# MBedRoom_BaseBoard.net
KiCad netlist of a schematic drawn in EasyEDA
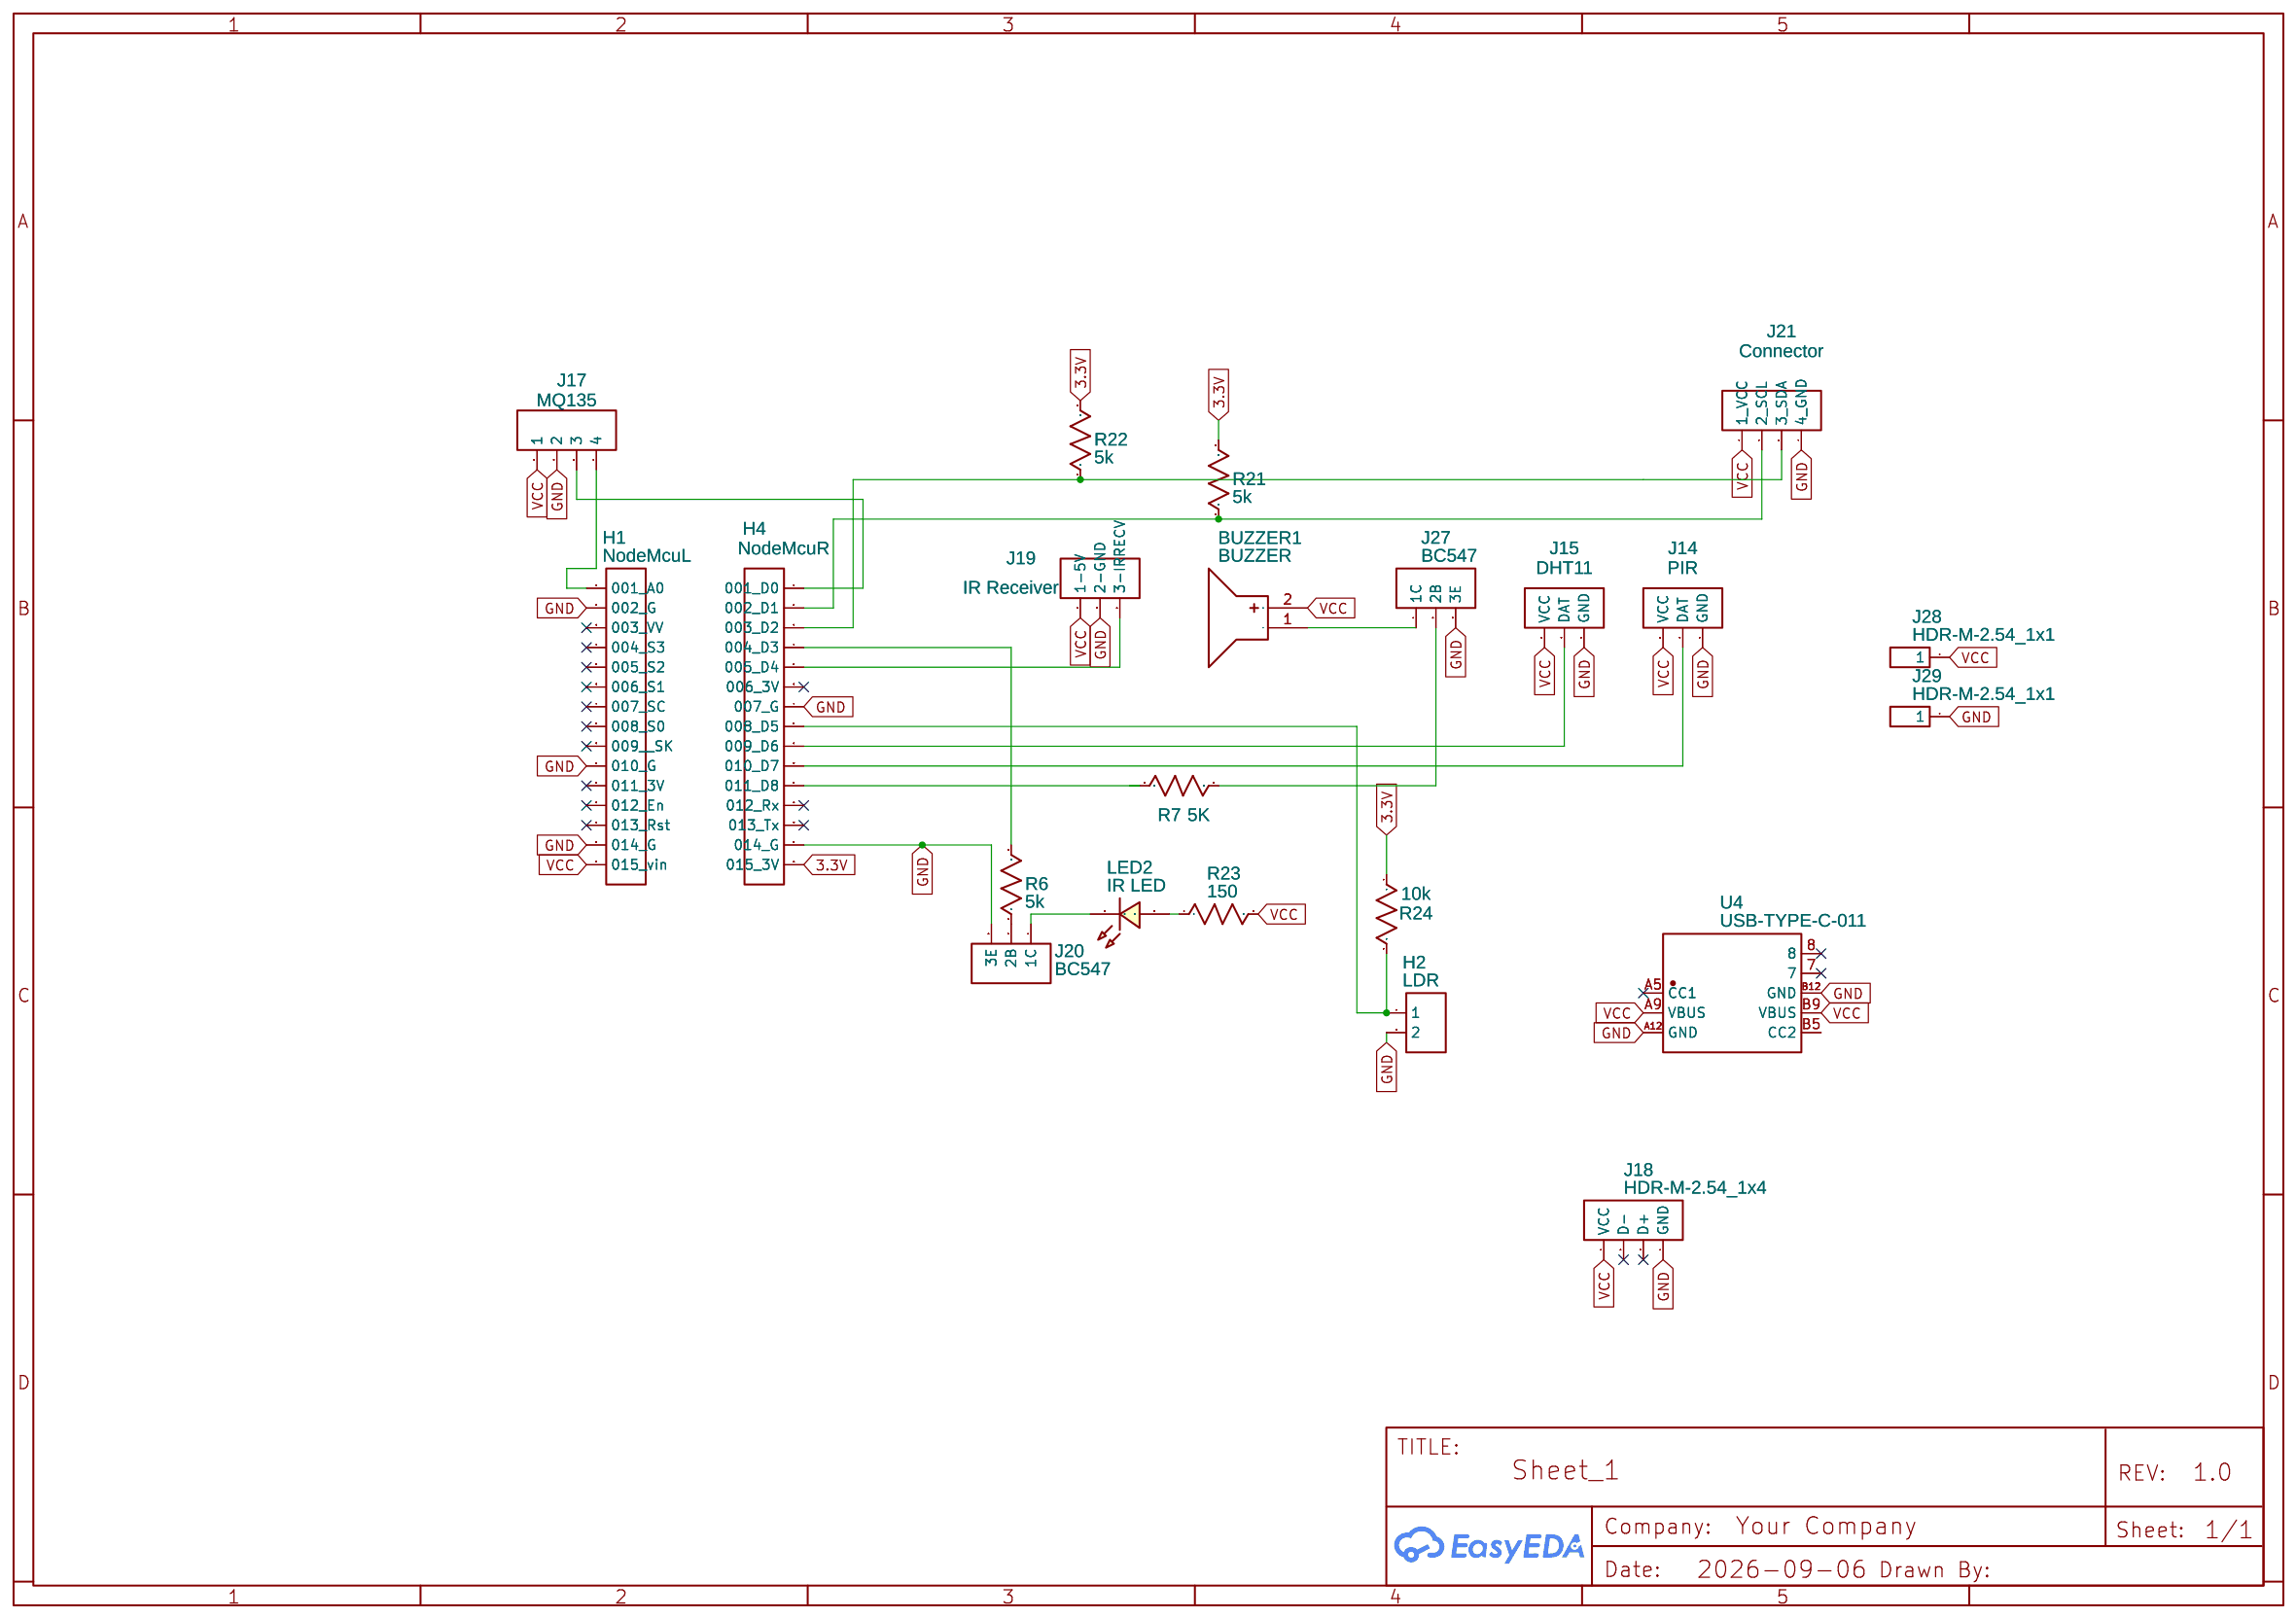
[diagram p0: schematic sheet]

(export (version "E")
  (design (tool "Eeschema 10.0.6"))
  (components
    (comp (ref "BUZZER1")
      (value "BUZZER")
      (fields (field (name "Manufacturer Part") "buzzer"))
      (libsource (lib "") (part "BUZZER"))
    )
    (comp (ref "H1") (value "NodeMcuL") (libsource (lib "") (part "HDR-F-2.54_1x15")))
    (comp (ref "H2") (value "LDR") (libsource (lib "") (part "HDR-F-2.54_1x2")))
    (comp (ref "H4") (value "NodeMcuR") (libsource (lib "") (part "HDR-F-2.54_1x15_1")))
    (comp (ref "J14") (value "PIR") (libsource (lib "") (part "HDR-M-2.54_1x3")))
    (comp (ref "J15") (value "DHT11") (libsource (lib "") (part "HDR-M-2.54_1x3")))
    (comp (ref "J17") (value "MQ135") (libsource (lib "") (part "HDR-M-2.54_1x4_2")))
    (comp (ref "J18") (value "HDR-M-2.54_1x4") (libsource (lib "") (part "HDR-M-2.54_1x4_1")))
    (comp (ref "J19") (value "IR Receiver") (libsource (lib "") (part "HDR-M-2.54_1x3_1")))
    (comp (ref "J20") (value "BC547") (libsource (lib "") (part "HDR-M-2.54_1x3_3")))
    (comp (ref "J21") (value "Connector") (libsource (lib "") (part "HDR-M-2.54_1x4")))
    (comp (ref "J27") (value "BC547") (libsource (lib "") (part "HDR-M-2.54_1x3_2")))
    (comp (ref "J28") (value "HDR-M-2.54_1x1") (libsource (lib "") (part "HDR-M-2.54_1x1")))
    (comp (ref "J29") (value "HDR-M-2.54_1x1") (libsource (lib "") (part "HDR-M-2.54_1x1")))
    (comp (ref "LED2")
      (value "IR LED")
      (fields
        (field (name "Manufacturer Part") "333-2SURD/S530-A3")
        (field (name "Manufacturer") "EVERLIGHT(台湾亿光)")
      )
      (libsource (lib "") (part "LED-TH-5mm_R"))
    )
    (comp (ref "R6") (value "5k") (libsource (lib "") (part "R_AXIAL-0.4_US")))
    (comp (ref "R7") (value "5K") (libsource (lib "") (part "R_AXIAL-0.4_US_1")))
    (comp (ref "R21") (value "5k") (libsource (lib "") (part "R_AXIAL-0.4_US")))
    (comp (ref "R22") (value "5k") (libsource (lib "") (part "R_AXIAL-0.4_US")))
    (comp (ref "R23") (value "150") (libsource (lib "") (part "R_AXIAL-0.4_US_1")))
    (comp (ref "R24") (value "10k") (libsource (lib "") (part "R_AXIAL-0.3_US")))
    (comp (ref "U4")
      (value "USB-TYPE-C-011")
      (fields (field (name "Manufacturer") "DEALON(德艺隆)"))
      (libsource (lib "") (part "USB-TYPE-C-011"))
    )
  )
  (nets
    (net (code "1") (name "3.3V") (class "Default")
      (node (ref "H4") (pin "15") (pinfunction "015_3V_15") (pintype "unspecified"))
      (node (ref "R21") (pin "2") (pinfunction "2_2") (pintype "unspecified"))
      (node (ref "R22") (pin "2") (pinfunction "2_2") (pintype "unspecified"))
      (node (ref "R24") (pin "1") (pinfunction "1_1") (pintype "unspecified"))
    )
    (net (code "2") (name "GND") (class "Default")
      (node (ref "H1") (pin "10") (pinfunction "010_G_10") (pintype "unspecified"))
      (node (ref "H1") (pin "14") (pinfunction "014_G_14") (pintype "unspecified"))
      (node (ref "H1") (pin "2") (pinfunction "002_G_2") (pintype "unspecified"))
      (node (ref "H2") (pin "2") (pinfunction "2_2") (pintype "input"))
      (node (ref "H4") (pin "14") (pinfunction "014_G_14") (pintype "unspecified"))
      (node (ref "H4") (pin "7") (pinfunction "007_G_7") (pintype "unspecified"))
      (node (ref "J14") (pin "1") (pinfunction "GND_1") (pintype "input"))
      (node (ref "J15") (pin "1") (pinfunction "GND_1") (pintype "input"))
      (node (ref "J17") (pin "2") (pinfunction "2_2") (pintype "unspecified"))
      (node (ref "J18") (pin "4") (pinfunction "GND_4") (pintype "unspecified"))
      (node (ref "J19") (pin "2") (pinfunction "2-GND_2") (pintype "input"))
      (node (ref "J20") (pin "3") (pinfunction "3E_3") (pintype "input"))
      (node (ref "J21") (pin "4") (pinfunction "4_GND_4") (pintype "unspecified"))
      (node (ref "J27") (pin "3") (pinfunction "3E_3") (pintype "input"))
      (node (ref "J29") (pin "1") (pinfunction "1_1") (pintype "input"))
      (node (ref "U4") (pin "A12") (pinfunction "GND_A12") (pintype "unspecified"))
      (node (ref "U4") (pin "B12") (pinfunction "GND_B12") (pintype "unspecified"))
    )
    (net (code "3") (name "Net-(BUZZER1--)") (class "Default")
      (node (ref "BUZZER1") (pin "1") (pinfunction "-_1") (pintype "unspecified"))
      (node (ref "J27") (pin "1") (pinfunction "1C_1") (pintype "input"))
    )
    (net (code "4") (name "Net-(H1-001_A0)") (class "Default")
      (node (ref "H1") (pin "1") (pinfunction "001_A0_1") (pintype "unspecified"))
      (node (ref "J17") (pin "4") (pinfunction "4_4") (pintype "unspecified"))
    )
    (net (code "5") (name "Net-(H4-001_D0)") (class "Default")
      (node (ref "H4") (pin "1") (pinfunction "001_D0_1") (pintype "unspecified"))
      (node (ref "J17") (pin "3") (pinfunction "3_3") (pintype "unspecified"))
    )
    (net (code "6") (name "Net-(H4-002_D1)") (class "Default")
      (node (ref "H4") (pin "2") (pinfunction "002_D1_2") (pintype "unspecified"))
      (node (ref "J21") (pin "2") (pinfunction "2_SCL_2") (pintype "unspecified"))
      (node (ref "R21") (pin "1") (pinfunction "1_1") (pintype "unspecified"))
    )
    (net (code "7") (name "Net-(H4-003_D2)") (class "Default")
      (node (ref "H4") (pin "3") (pinfunction "003_D2_3") (pintype "unspecified"))
      (node (ref "J21") (pin "3") (pinfunction "3_SDA_3") (pintype "unspecified"))
      (node (ref "R22") (pin "1") (pinfunction "1_1") (pintype "unspecified"))
    )
    (net (code "8") (name "Net-(H4-004_D3)") (class "Default")
      (node (ref "H4") (pin "4") (pinfunction "004_D3_4") (pintype "unspecified"))
      (node (ref "R6") (pin "2") (pinfunction "2_2") (pintype "unspecified"))
    )
    (net (code "9") (name "Net-(H4-005_D4)") (class "Default")
      (node (ref "H4") (pin "5") (pinfunction "005_D4_5") (pintype "unspecified"))
      (node (ref "J19") (pin "3") (pinfunction "3-IRRECV_3") (pintype "input"))
    )
    (net (code "10") (name "Net-(H4-008_D5)") (class "Default")
      (node (ref "H2") (pin "1") (pinfunction "1_1") (pintype "input"))
      (node (ref "H4") (pin "8") (pinfunction "008_D5_8") (pintype "unspecified"))
      (node (ref "R24") (pin "2") (pinfunction "2_2") (pintype "unspecified"))
    )
    (net (code "11") (name "Net-(H4-009_D6)") (class "Default")
      (node (ref "H4") (pin "9") (pinfunction "009_D6_9") (pintype "unspecified"))
      (node (ref "J15") (pin "2") (pinfunction "DAT_2") (pintype "input"))
    )
    (net (code "12") (name "Net-(H4-010_D7)") (class "Default")
      (node (ref "H4") (pin "10") (pinfunction "010_D7_10") (pintype "unspecified"))
      (node (ref "J14") (pin "2") (pinfunction "DAT_2") (pintype "input"))
    )
    (net (code "13") (name "Net-(H4-011_D8)") (class "Default")
      (node (ref "H4") (pin "11") (pinfunction "011_D8_11") (pintype "unspecified"))
      (node (ref "R7") (pin "1") (pinfunction "1_1") (pintype "unspecified"))
    )
    (net (code "14") (name "Net-(J20-1C)") (class "Default")
      (node (ref "J20") (pin "1") (pinfunction "1C_1") (pintype "input"))
      (node (ref "LED2") (pin "2") (pinfunction "2_2") (pintype "unspecified"))
    )
    (net (code "15") (name "Net-(J20-2B)") (class "Default")
      (node (ref "J20") (pin "2") (pinfunction "2B_2") (pintype "input"))
      (node (ref "R6") (pin "1") (pinfunction "1_1") (pintype "unspecified"))
    )
    (net (code "16") (name "Net-(J27-2B)") (class "Default")
      (node (ref "J27") (pin "2") (pinfunction "2B_2") (pintype "input"))
      (node (ref "R7") (pin "2") (pinfunction "2_2") (pintype "unspecified"))
    )
    (net (code "17") (name "Net-(LED2-Pad1)") (class "Default")
      (node (ref "LED2") (pin "1") (pinfunction "1_1") (pintype "unspecified"))
      (node (ref "R23") (pin "1") (pinfunction "1_1") (pintype "unspecified"))
    )
    (net (code "18") (name "VCC") (class "Default")
      (node (ref "BUZZER1") (pin "2") (pinfunction "+_2") (pintype "unspecified"))
      (node (ref "H1") (pin "15") (pinfunction "015_vin_15") (pintype "unspecified"))
      (node (ref "J14") (pin "3") (pinfunction "VCC_3") (pintype "input"))
      (node (ref "J15") (pin "3") (pinfunction "VCC_3") (pintype "input"))
      (node (ref "J17") (pin "1") (pinfunction "1_1") (pintype "unspecified"))
      (node (ref "J18") (pin "1") (pinfunction "VCC_1") (pintype "unspecified"))
      (node (ref "J19") (pin "1") (pinfunction "1-5V_1") (pintype "input"))
      (node (ref "J21") (pin "1") (pinfunction "1_VCC_1") (pintype "unspecified"))
      (node (ref "J28") (pin "1") (pinfunction "1_1") (pintype "input"))
      (node (ref "R23") (pin "2") (pinfunction "2_2") (pintype "unspecified"))
      (node (ref "U4") (pin "A9") (pinfunction "VBUS_A9") (pintype "unspecified"))
      (node (ref "U4") (pin "B9") (pinfunction "VBUS_B9") (pintype "unspecified"))
    )
    (net (code "19") (name "unconnected-(H1-003_VV-Pad3)") (class "Default")
      (node (ref "H1") (pin "3") (pinfunction "003_VV_3") (pintype "unspecified+no_connect"))
    )
    (net (code "20") (name "unconnected-(H1-004_S3-Pad4)") (class "Default")
      (node (ref "H1") (pin "4") (pinfunction "004_S3_4") (pintype "unspecified+no_connect"))
    )
    (net (code "21") (name "unconnected-(H1-005_S2-Pad5)") (class "Default")
      (node (ref "H1") (pin "5") (pinfunction "005_S2_5") (pintype "unspecified+no_connect"))
    )
    (net (code "22") (name "unconnected-(H1-006_S1-Pad6)") (class "Default")
      (node (ref "H1") (pin "6") (pinfunction "006_S1_6") (pintype "unspecified+no_connect"))
    )
    (net (code "23") (name "unconnected-(H1-007_SC-Pad7)") (class "Default")
      (node (ref "H1") (pin "7") (pinfunction "007_SC_7") (pintype "unspecified+no_connect"))
    )
    (net (code "24") (name "unconnected-(H1-008_S0-Pad8)") (class "Default")
      (node (ref "H1") (pin "8") (pinfunction "008_S0_8") (pintype "unspecified+no_connect"))
    )
    (net (code "25") (name "unconnected-(H1-009__SK-Pad9)") (class "Default")
      (node (ref "H1") (pin "9") (pinfunction "009__SK_9") (pintype "unspecified+no_connect"))
    )
    (net (code "26") (name "unconnected-(H1-011_3V-Pad11)") (class "Default")
      (node (ref "H1") (pin "11") (pinfunction "011_3V_11") (pintype "unspecified+no_connect"))
    )
    (net (code "27") (name "unconnected-(H1-012_En-Pad12)") (class "Default")
      (node (ref "H1") (pin "12") (pinfunction "012_En_12") (pintype "unspecified+no_connect"))
    )
    (net (code "28") (name "unconnected-(H1-013_Rst-Pad13)") (class "Default")
      (node (ref "H1") (pin "13") (pinfunction "013_Rst_13") (pintype "unspecified+no_connect"))
    )
    (net (code "29") (name "unconnected-(H4-006_3V-Pad6)") (class "Default")
      (node (ref "H4") (pin "6") (pinfunction "006_3V_6") (pintype "unspecified+no_connect"))
    )
    (net (code "30") (name "unconnected-(H4-012_Rx-Pad12)") (class "Default")
      (node (ref "H4") (pin "12") (pinfunction "012_Rx_12") (pintype "unspecified+no_connect"))
    )
    (net (code "31") (name "unconnected-(H4-013_Tx-Pad13)") (class "Default")
      (node (ref "H4") (pin "13") (pinfunction "013_Tx_13") (pintype "unspecified+no_connect"))
    )
    (net (code "32") (name "unconnected-(J18-D+-Pad3)") (class "Default")
      (node (ref "J18") (pin "3") (pinfunction "D+_3") (pintype "unspecified+no_connect"))
    )
    (net (code "33") (name "unconnected-(J18-D--Pad2)") (class "Default")
      (node (ref "J18") (pin "2") (pinfunction "D-_2") (pintype "unspecified+no_connect"))
    )
    (net (code "34") (name "unconnected-(U4-CC1-PadA5)") (class "Default")
      (node (ref "U4") (pin "A5") (pinfunction "CC1_A5") (pintype "unspecified+no_connect"))
    )
    (net (code "35") (name "unconnected-(U4-CC2-PadB5)") (class "Default")
      (node (ref "U4") (pin "B5") (pinfunction "CC2_B5") (pintype "unspecified"))
    )
    (net (code "36") (name "unconnected-(U4-Pad7)") (class "Default")
      (node (ref "U4") (pin "7") (pinfunction "7_7") (pintype "unspecified+no_connect"))
    )
    (net (code "37") (name "unconnected-(U4-Pad8)") (class "Default")
      (node (ref "U4") (pin "8") (pinfunction "8_8") (pintype "unspecified+no_connect"))
    )
  )
)
